# LEDs.net
KiCad netlist of a schematic drawn in Altium Designer
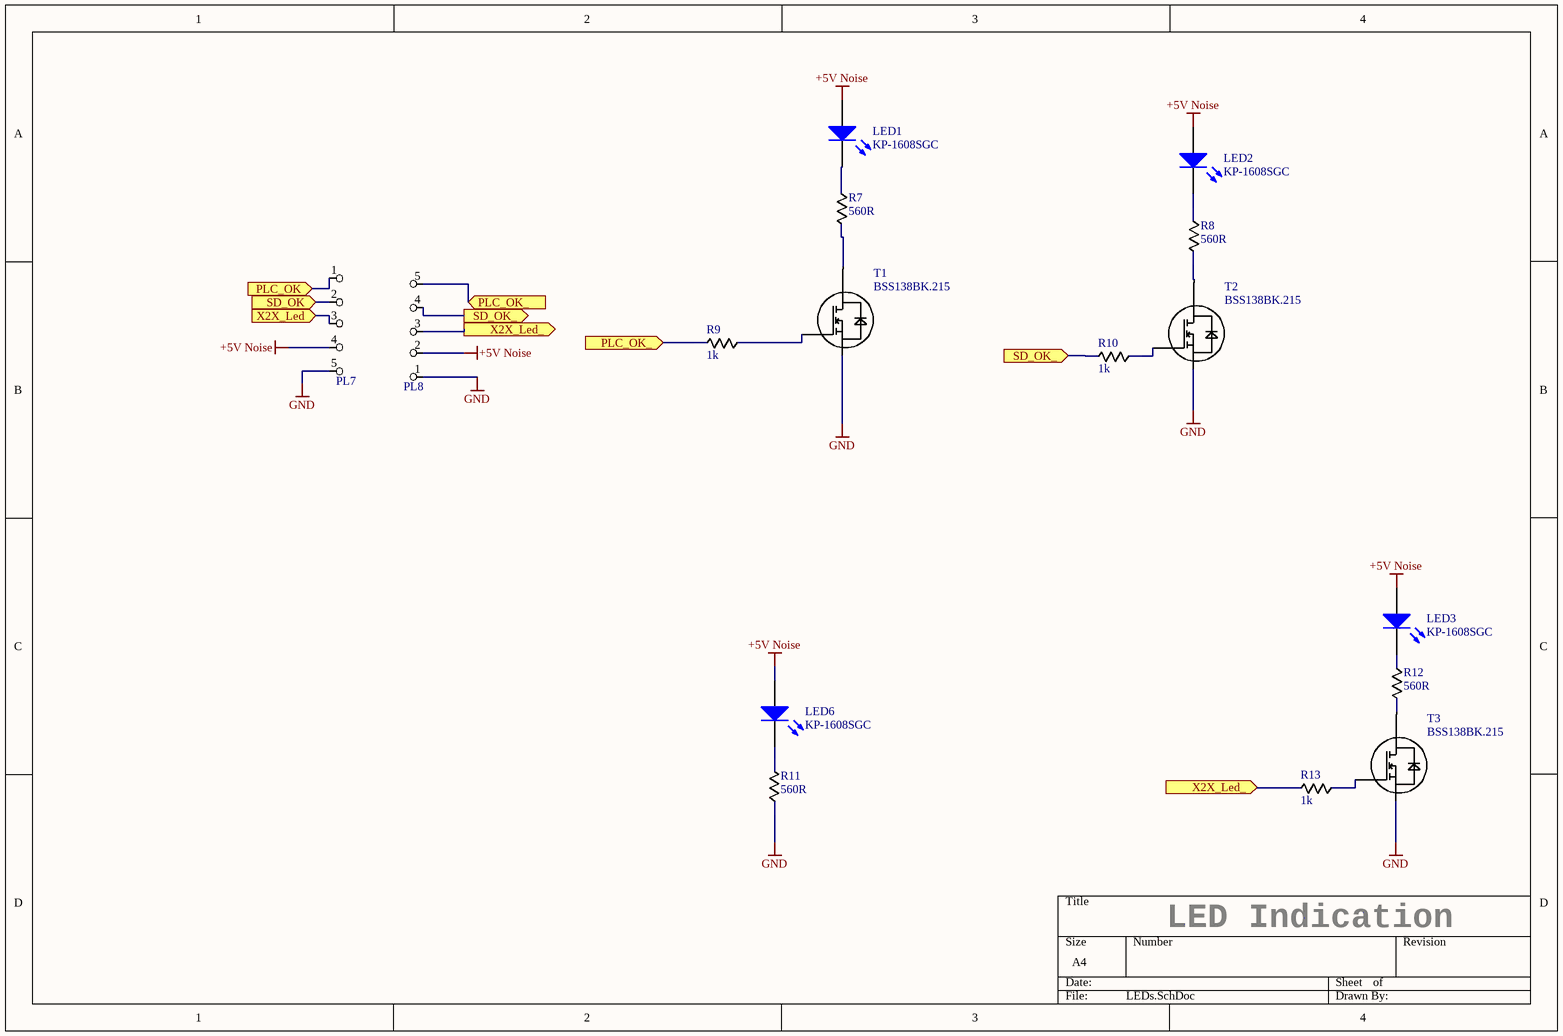
[diagram p0: LEDs.SchDoc]

(export (version "E")
  (design (tool "Eeschema 10.0.6"))
  (components
    (comp (ref "LED1")
      (value "KP-1608SGC")
      (footprint "0603")
      (fields (field (name "PUBLISHER") "Altium Limited"))
      (libsource (lib "kontr") (part "0603 LED"))
    )
    (comp (ref "LED2")
      (value "KP-1608SGC")
      (footprint "0603")
      (fields (field (name "PUBLISHER") "Altium Limited"))
      (libsource (lib "kontr") (part "0603 LED"))
    )
    (comp (ref "LED3")
      (value "KP-1608SGC")
      (footprint "0603")
      (fields (field (name "PUBLISHER") "Altium Limited"))
      (libsource (lib "kontr") (part "0603 LED"))
    )
    (comp (ref "LED6")
      (value "KP-1608SGC")
      (footprint "0603")
      (fields (field (name "PUBLISHER") "Altium Limited"))
      (libsource (lib "kontr") (part "0603 LED"))
    )
    (comp (ref "PL7")
      (value "plug")
      (footprint "PLS 5")
      (description "PLS-5R (DS1022-1x5R)")
      (libsource (lib "kontr") (part "PLS-5R"))
    )
    (comp (ref "PL8")
      (value "plug")
      (footprint "PLS 5")
      (description "PLS-5R (DS1022-1x5R)")
      (libsource (lib "kontr") (part "PLS-5R"))
    )
    (comp (ref "R7")
      (value "560R")
      (footprint "0603")
      (description "RC0603JR-07560RL")
      (libsource (lib "kontr") (part "0603 RES"))
    )
    (comp (ref "R8")
      (value "560R")
      (footprint "0603")
      (description "RC0603JR-07560RL")
      (libsource (lib "kontr") (part "0603 RES"))
    )
    (comp (ref "R9")
      (value "1k")
      (footprint "0603")
      (description "RC0603FR-071KL")
      (libsource (lib "kontr") (part "0603 RES"))
    )
    (comp (ref "R10")
      (value "1k")
      (footprint "0603")
      (description "RC0603FR-071KL")
      (libsource (lib "kontr") (part "0603 RES"))
    )
    (comp (ref "R11")
      (value "560R")
      (footprint "0603")
      (description "RC0603JR-07560RL")
      (libsource (lib "kontr") (part "0603 RES"))
    )
    (comp (ref "R12")
      (value "560R")
      (footprint "0603")
      (description "RC0603JR-07560RL")
      (libsource (lib "kontr") (part "0603 RES"))
    )
    (comp (ref "R13")
      (value "1k")
      (footprint "0603")
      (description "RC0603FR-071KL")
      (libsource (lib "kontr") (part "0603 RES"))
    )
    (comp (ref "T1") (value "BSS138BK.215") (footprint "SOT23") (libsource (lib "kontr") (part "BSS138")))
    (comp (ref "T2") (value "BSS138BK.215") (footprint "SOT23") (libsource (lib "kontr") (part "BSS138")))
    (comp (ref "T3") (value "BSS138BK.215") (footprint "SOT23") (libsource (lib "kontr") (part "BSS138")))
  )
  (nets
    (net (code "1") (name "+5V Noise") (class "Default")
      (node (ref "LED1") (pin "1") (pinfunction "A_1") (pintype "passive"))
      (node (ref "LED2") (pin "1") (pinfunction "A_1") (pintype "passive"))
      (node (ref "LED3") (pin "1") (pinfunction "A_1") (pintype "passive"))
      (node (ref "LED6") (pin "1") (pinfunction "A_1") (pintype "passive"))
      (node (ref "PL7") (pin "4") (pinfunction "2_4") (pintype "passive"))
      (node (ref "PL8") (pin "2") (pinfunction "2_2") (pintype "passive"))
    )
    (net (code "2") (name "/PLC_OK") (class "Default")
      (node (ref "PL7") (pin "1") (pinfunction "1_1") (pintype "passive"))
    )
    (net (code "3") (name "/PLC_OK_") (class "Default")
      (node (ref "PL8") (pin "5") (pinfunction "2_5") (pintype "passive"))
      (node (ref "R9") (pin "2") (pintype "passive"))
    )
    (net (code "4") (name "/SD_OK") (class "Default")
      (node (ref "PL7") (pin "2") (pinfunction "2_2") (pintype "passive"))
    )
    (net (code "5") (name "/SD_OK_") (class "Default")
      (node (ref "PL8") (pin "4") (pinfunction "2_4") (pintype "passive"))
      (node (ref "R10") (pin "2") (pintype "passive"))
    )
    (net (code "6") (name "/X2X_Led") (class "Default")
      (node (ref "PL7") (pin "3") (pinfunction "1_3") (pintype "passive"))
    )
    (net (code "7") (name "/X2X_Led_") (class "Default")
      (node (ref "PL8") (pin "3") (pinfunction "1_3") (pintype "passive"))
      (node (ref "R13") (pin "2") (pintype "passive"))
    )
    (net (code "8") (name "GND") (class "Default")
      (node (ref "PL7") (pin "5") (pinfunction "2_5") (pintype "passive"))
      (node (ref "PL8") (pin "1") (pinfunction "1_1") (pintype "passive"))
      (node (ref "R11") (pin "1") (pintype "passive"))
      (node (ref "T1") (pin "2") (pinfunction "S_2") (pintype "passive"))
      (node (ref "T2") (pin "2") (pinfunction "S_2") (pintype "passive"))
      (node (ref "T3") (pin "2") (pinfunction "S_2") (pintype "passive"))
    )
    (net (code "9") (name "Net-(LED1-K)") (class "Default")
      (node (ref "LED1") (pin "2") (pinfunction "K_2") (pintype "passive"))
      (node (ref "R7") (pin "1") (pintype "passive"))
    )
    (net (code "10") (name "Net-(LED2-K)") (class "Default")
      (node (ref "LED2") (pin "2") (pinfunction "K_2") (pintype "passive"))
      (node (ref "R8") (pin "1") (pintype "passive"))
    )
    (net (code "11") (name "Net-(LED3-K)") (class "Default")
      (node (ref "LED3") (pin "2") (pinfunction "K_2") (pintype "passive"))
      (node (ref "R12") (pin "1") (pintype "passive"))
    )
    (net (code "12") (name "Net-(LED6-K)") (class "Default")
      (node (ref "LED6") (pin "2") (pinfunction "K_2") (pintype "passive"))
      (node (ref "R11") (pin "2") (pintype "passive"))
    )
    (net (code "13") (name "Net-(T1-D)") (class "Default")
      (node (ref "R7") (pin "2") (pintype "passive"))
      (node (ref "T1") (pin "3") (pinfunction "D_3") (pintype "passive"))
    )
    (net (code "14") (name "Net-(T1-G)") (class "Default")
      (node (ref "R9") (pin "1") (pintype "passive"))
      (node (ref "T1") (pin "1") (pinfunction "G_1") (pintype "passive"))
    )
    (net (code "15") (name "Net-(T2-D)") (class "Default")
      (node (ref "R8") (pin "2") (pintype "passive"))
      (node (ref "T2") (pin "3") (pinfunction "D_3") (pintype "passive"))
    )
    (net (code "16") (name "Net-(T2-G)") (class "Default")
      (node (ref "R10") (pin "1") (pintype "passive"))
      (node (ref "T2") (pin "1") (pinfunction "G_1") (pintype "passive"))
    )
    (net (code "17") (name "Net-(T3-D)") (class "Default")
      (node (ref "R12") (pin "2") (pintype "passive"))
      (node (ref "T3") (pin "3") (pinfunction "D_3") (pintype "passive"))
    )
    (net (code "18") (name "Net-(T3-G)") (class "Default")
      (node (ref "R13") (pin "1") (pintype "passive"))
      (node (ref "T3") (pin "1") (pinfunction "G_1") (pintype "passive"))
    )
  )
)
